# Sheet1.net
KiCad netlist of a schematic drawn in Altium Designer
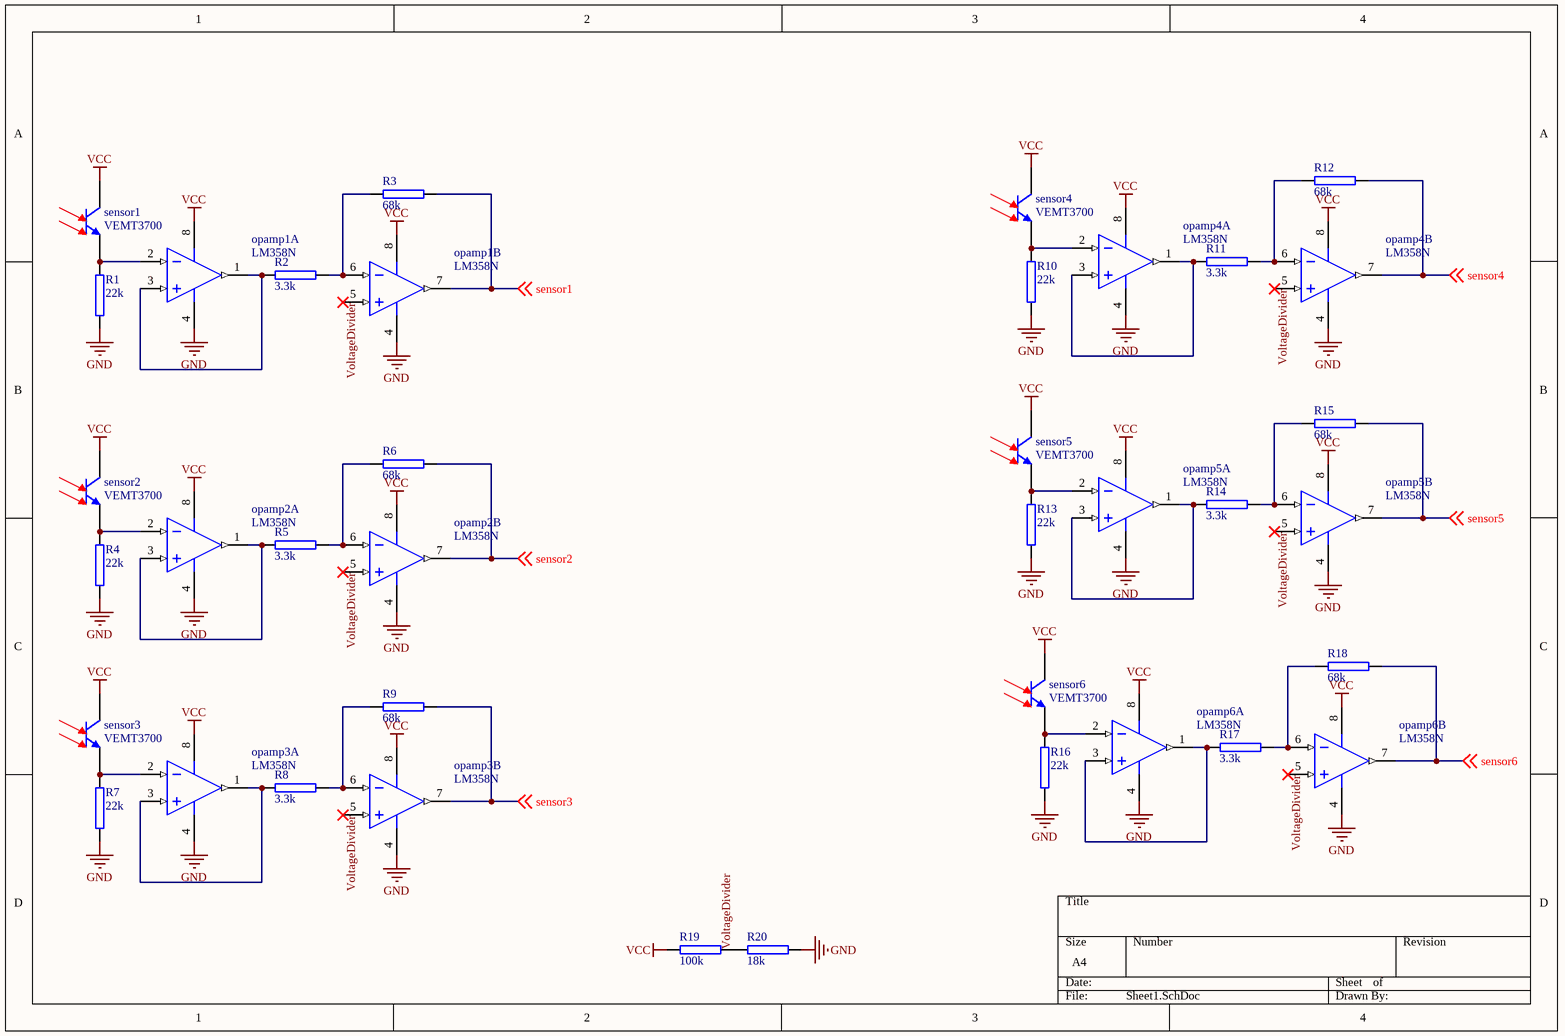
[diagram p0: Sheet1.SchDoc]

(export (version "E")
  (design (tool "Eeschema 10.0.6"))
  (components
    (comp (ref "opamp1")
      (value "LM358N")
      (footprint "N08E")
      (description "Low Power Dual Operational Amplifier, 8-pin MDIP")
      (fields
        (field (name "MANUFACTURER") "National Semiconductor")
        (field (name "PUBLISHER") "Altium Limited")
      )
      (libsource (lib "NSC Amplifier") (part "LM358N"))
    )
    (comp (ref "opamp2")
      (value "LM358N")
      (footprint "N08E")
      (description "Low Power Dual Operational Amplifier, 8-pin MDIP")
      (fields
        (field (name "MANUFACTURER") "National Semiconductor")
        (field (name "PUBLISHER") "Altium Limited")
      )
      (libsource (lib "NSC Amplifier") (part "LM358N"))
    )
    (comp (ref "opamp3")
      (value "LM358N")
      (footprint "N08E")
      (description "Low Power Dual Operational Amplifier, 8-pin MDIP")
      (fields
        (field (name "MANUFACTURER") "National Semiconductor")
        (field (name "PUBLISHER") "Altium Limited")
      )
      (libsource (lib "NSC Amplifier") (part "LM358N"))
    )
    (comp (ref "opamp4")
      (value "LM358N")
      (footprint "N08E")
      (description "Low Power Dual Operational Amplifier, 8-pin MDIP")
      (fields
        (field (name "MANUFACTURER") "National Semiconductor")
        (field (name "PUBLISHER") "Altium Limited")
      )
      (libsource (lib "NSC Amplifier") (part "LM358N"))
    )
    (comp (ref "opamp5")
      (value "LM358N")
      (footprint "N08E")
      (description "Low Power Dual Operational Amplifier, 8-pin MDIP")
      (fields
        (field (name "MANUFACTURER") "National Semiconductor")
        (field (name "PUBLISHER") "Altium Limited")
      )
      (libsource (lib "NSC Amplifier") (part "LM358N"))
    )
    (comp (ref "opamp6")
      (value "LM358N")
      (footprint "N08E")
      (description "Low Power Dual Operational Amplifier, 8-pin MDIP")
      (fields
        (field (name "MANUFACTURER") "National Semiconductor")
        (field (name "PUBLISHER") "Altium Limited")
      )
      (libsource (lib "NSC Amplifier") (part "LM358N"))
    )
    (comp (ref "R1") (value "22k") (footprint "AXIAL0.4") (libsource (lib "COMSYS301_2013") (part "RES2")))
    (comp (ref "R2") (value "3.3k") (footprint "AXIAL0.4") (libsource (lib "COMSYS301_2013") (part "RES2")))
    (comp (ref "R3") (value "68k") (footprint "AXIAL0.4") (libsource (lib "COMSYS301_2013") (part "RES2")))
    (comp (ref "R4") (value "22k") (footprint "AXIAL0.4") (libsource (lib "COMSYS301_2013") (part "RES2")))
    (comp (ref "R5") (value "3.3k") (footprint "AXIAL0.4") (libsource (lib "COMSYS301_2013") (part "RES2")))
    (comp (ref "R6") (value "68k") (footprint "AXIAL0.4") (libsource (lib "COMSYS301_2013") (part "RES2")))
    (comp (ref "R7") (value "22k") (footprint "AXIAL0.4") (libsource (lib "COMSYS301_2013") (part "RES2")))
    (comp (ref "R8") (value "3.3k") (footprint "AXIAL0.4") (libsource (lib "COMSYS301_2013") (part "RES2")))
    (comp (ref "R9") (value "68k") (footprint "AXIAL0.4") (libsource (lib "COMSYS301_2013") (part "RES2")))
    (comp (ref "R10") (value "22k") (footprint "AXIAL0.4") (libsource (lib "COMSYS301_2013") (part "RES2")))
    (comp (ref "R11") (value "3.3k") (footprint "AXIAL0.4") (libsource (lib "COMSYS301_2013") (part "RES2")))
    (comp (ref "R12") (value "68k") (footprint "AXIAL0.4") (libsource (lib "COMSYS301_2013") (part "RES2")))
    (comp (ref "R13") (value "22k") (footprint "AXIAL0.4") (libsource (lib "COMSYS301_2013") (part "RES2")))
    (comp (ref "R14") (value "3.3k") (footprint "AXIAL0.4") (libsource (lib "COMSYS301_2013") (part "RES2")))
    (comp (ref "R15") (value "68k") (footprint "AXIAL0.4") (libsource (lib "COMSYS301_2013") (part "RES2")))
    (comp (ref "R16") (value "22k") (footprint "AXIAL0.4") (libsource (lib "COMSYS301_2013") (part "RES2")))
    (comp (ref "R17") (value "3.3k") (footprint "AXIAL0.4") (libsource (lib "COMSYS301_2013") (part "RES2")))
    (comp (ref "R18") (value "68k") (footprint "AXIAL0.4") (libsource (lib "COMSYS301_2013") (part "RES2")))
    (comp (ref "R19") (value "100k") (footprint "AXIAL0.4") (libsource (lib "COMSYS301_2013") (part "RES2")))
    (comp (ref "R20") (value "18k") (footprint "AXIAL0.4") (libsource (lib "COMSYS301_2013") (part "RES2")))
    (comp (ref "sensor1")
      (value "VEMT3700")
      (footprint "VEMT3700")
      (description "Silicon NPN Phototransistor")
      (libsource (lib "COMSYS301_2013") (part "VEMT3700"))
    )
    (comp (ref "sensor2")
      (value "VEMT3700")
      (footprint "VEMT3700")
      (description "Silicon NPN Phototransistor")
      (libsource (lib "COMSYS301_2013") (part "VEMT3700"))
    )
    (comp (ref "sensor3")
      (value "VEMT3700")
      (footprint "VEMT3700")
      (description "Silicon NPN Phototransistor")
      (libsource (lib "COMSYS301_2013") (part "VEMT3700"))
    )
    (comp (ref "sensor4")
      (value "VEMT3700")
      (footprint "VEMT3700")
      (description "Silicon NPN Phototransistor")
      (libsource (lib "COMSYS301_2013") (part "VEMT3700"))
    )
    (comp (ref "sensor5")
      (value "VEMT3700")
      (footprint "VEMT3700")
      (description "Silicon NPN Phototransistor")
      (libsource (lib "COMSYS301_2013") (part "VEMT3700"))
    )
    (comp (ref "sensor6")
      (value "VEMT3700")
      (footprint "VEMT3700")
      (description "Silicon NPN Phototransistor")
      (libsource (lib "COMSYS301_2013") (part "VEMT3700"))
    )
  )
  (nets
    (net (code "1") (name "/VoltageDivider") (class "Default")
      (node (ref "R19") (pin "1") (pinfunction "1_1") (pintype "passive"))
      (node (ref "R20") (pin "1") (pinfunction "1_1") (pintype "passive"))
      (node (ref "opamp1") (pin "5") (pinfunction "INB+_5") (pintype "input"))
      (node (ref "opamp2") (pin "5") (pinfunction "INB+_5") (pintype "input"))
      (node (ref "opamp3") (pin "5") (pinfunction "INB+_5") (pintype "input"))
      (node (ref "opamp4") (pin "5") (pinfunction "INB+_5") (pintype "input"))
      (node (ref "opamp5") (pin "5") (pinfunction "INB+_5") (pintype "input"))
      (node (ref "opamp6") (pin "5") (pinfunction "INB+_5") (pintype "input"))
    )
    (net (code "2") (name "GND") (class "Default")
      (node (ref "R1") (pin "2") (pinfunction "2_2") (pintype "passive"))
      (node (ref "R10") (pin "2") (pinfunction "2_2") (pintype "passive"))
      (node (ref "R13") (pin "2") (pinfunction "2_2") (pintype "passive"))
      (node (ref "R16") (pin "2") (pinfunction "2_2") (pintype "passive"))
      (node (ref "R20") (pin "2") (pinfunction "2_2") (pintype "passive"))
      (node (ref "R4") (pin "2") (pinfunction "2_2") (pintype "passive"))
      (node (ref "R7") (pin "2") (pinfunction "2_2") (pintype "passive"))
      (node (ref "opamp1") (pin "4") (pinfunction "GND_4") (pintype "power_in"))
      (node (ref "opamp2") (pin "4") (pinfunction "GND_4") (pintype "power_in"))
      (node (ref "opamp3") (pin "4") (pinfunction "GND_4") (pintype "power_in"))
      (node (ref "opamp4") (pin "4") (pinfunction "GND_4") (pintype "power_in"))
      (node (ref "opamp5") (pin "4") (pinfunction "GND_4") (pintype "power_in"))
      (node (ref "opamp6") (pin "4") (pinfunction "GND_4") (pintype "power_in"))
    )
    (net (code "3") (name "Net-(opamp1A-INA+)") (class "Default")
      (node (ref "R2") (pin "1") (pinfunction "1_1") (pintype "passive"))
      (node (ref "opamp1") (pin "1") (pinfunction "OUTA_1") (pintype "output"))
      (node (ref "opamp1") (pin "3") (pinfunction "INA+_3") (pintype "input"))
    )
    (net (code "4") (name "Net-(opamp1A-INA-)") (class "Default")
      (node (ref "R1") (pin "1") (pinfunction "1_1") (pintype "passive"))
      (node (ref "opamp1") (pin "2") (pinfunction "INA-_2") (pintype "input"))
      (node (ref "sensor1") (pin "2") (pinfunction "E_2") (pintype "passive"))
    )
    (net (code "5") (name "Net-(opamp1B-INB-)") (class "Default")
      (node (ref "R2") (pin "2") (pinfunction "2_2") (pintype "passive"))
      (node (ref "R3") (pin "1") (pinfunction "1_1") (pintype "passive"))
      (node (ref "opamp1") (pin "6") (pinfunction "INB-_6") (pintype "input"))
    )
    (net (code "6") (name "Net-(opamp2A-INA+)") (class "Default")
      (node (ref "R5") (pin "1") (pinfunction "1_1") (pintype "passive"))
      (node (ref "opamp2") (pin "1") (pinfunction "OUTA_1") (pintype "output"))
      (node (ref "opamp2") (pin "3") (pinfunction "INA+_3") (pintype "input"))
    )
    (net (code "7") (name "Net-(opamp2A-INA-)") (class "Default")
      (node (ref "R4") (pin "1") (pinfunction "1_1") (pintype "passive"))
      (node (ref "opamp2") (pin "2") (pinfunction "INA-_2") (pintype "input"))
      (node (ref "sensor2") (pin "2") (pinfunction "E_2") (pintype "passive"))
    )
    (net (code "8") (name "Net-(opamp2B-INB-)") (class "Default")
      (node (ref "R5") (pin "2") (pinfunction "2_2") (pintype "passive"))
      (node (ref "R6") (pin "1") (pinfunction "1_1") (pintype "passive"))
      (node (ref "opamp2") (pin "6") (pinfunction "INB-_6") (pintype "input"))
    )
    (net (code "9") (name "Net-(opamp3A-INA+)") (class "Default")
      (node (ref "R8") (pin "1") (pinfunction "1_1") (pintype "passive"))
      (node (ref "opamp3") (pin "1") (pinfunction "OUTA_1") (pintype "output"))
      (node (ref "opamp3") (pin "3") (pinfunction "INA+_3") (pintype "input"))
    )
    (net (code "10") (name "Net-(opamp3A-INA-)") (class "Default")
      (node (ref "R7") (pin "1") (pinfunction "1_1") (pintype "passive"))
      (node (ref "opamp3") (pin "2") (pinfunction "INA-_2") (pintype "input"))
      (node (ref "sensor3") (pin "2") (pinfunction "E_2") (pintype "passive"))
    )
    (net (code "11") (name "Net-(opamp3B-INB-)") (class "Default")
      (node (ref "R8") (pin "2") (pinfunction "2_2") (pintype "passive"))
      (node (ref "R9") (pin "1") (pinfunction "1_1") (pintype "passive"))
      (node (ref "opamp3") (pin "6") (pinfunction "INB-_6") (pintype "input"))
    )
    (net (code "12") (name "Net-(opamp4A-INA+)") (class "Default")
      (node (ref "R11") (pin "1") (pinfunction "1_1") (pintype "passive"))
      (node (ref "opamp4") (pin "1") (pinfunction "OUTA_1") (pintype "output"))
      (node (ref "opamp4") (pin "3") (pinfunction "INA+_3") (pintype "input"))
    )
    (net (code "13") (name "Net-(opamp4A-INA-)") (class "Default")
      (node (ref "R10") (pin "1") (pinfunction "1_1") (pintype "passive"))
      (node (ref "opamp4") (pin "2") (pinfunction "INA-_2") (pintype "input"))
      (node (ref "sensor4") (pin "2") (pinfunction "E_2") (pintype "passive"))
    )
    (net (code "14") (name "Net-(opamp4B-INB-)") (class "Default")
      (node (ref "R11") (pin "2") (pinfunction "2_2") (pintype "passive"))
      (node (ref "R12") (pin "1") (pinfunction "1_1") (pintype "passive"))
      (node (ref "opamp4") (pin "6") (pinfunction "INB-_6") (pintype "input"))
    )
    (net (code "15") (name "Net-(opamp5A-INA+)") (class "Default")
      (node (ref "R14") (pin "1") (pinfunction "1_1") (pintype "passive"))
      (node (ref "opamp5") (pin "1") (pinfunction "OUTA_1") (pintype "output"))
      (node (ref "opamp5") (pin "3") (pinfunction "INA+_3") (pintype "input"))
    )
    (net (code "16") (name "Net-(opamp5A-INA-)") (class "Default")
      (node (ref "R13") (pin "1") (pinfunction "1_1") (pintype "passive"))
      (node (ref "opamp5") (pin "2") (pinfunction "INA-_2") (pintype "input"))
      (node (ref "sensor5") (pin "2") (pinfunction "E_2") (pintype "passive"))
    )
    (net (code "17") (name "Net-(opamp5B-INB-)") (class "Default")
      (node (ref "R14") (pin "2") (pinfunction "2_2") (pintype "passive"))
      (node (ref "R15") (pin "1") (pinfunction "1_1") (pintype "passive"))
      (node (ref "opamp5") (pin "6") (pinfunction "INB-_6") (pintype "input"))
    )
    (net (code "18") (name "Net-(opamp6A-INA+)") (class "Default")
      (node (ref "R17") (pin "1") (pinfunction "1_1") (pintype "passive"))
      (node (ref "opamp6") (pin "1") (pinfunction "OUTA_1") (pintype "output"))
      (node (ref "opamp6") (pin "3") (pinfunction "INA+_3") (pintype "input"))
    )
    (net (code "19") (name "Net-(opamp6A-INA-)") (class "Default")
      (node (ref "R16") (pin "1") (pinfunction "1_1") (pintype "passive"))
      (node (ref "opamp6") (pin "2") (pinfunction "INA-_2") (pintype "input"))
      (node (ref "sensor6") (pin "2") (pinfunction "E_2") (pintype "passive"))
    )
    (net (code "20") (name "Net-(opamp6B-INB-)") (class "Default")
      (node (ref "R17") (pin "2") (pinfunction "2_2") (pintype "passive"))
      (node (ref "R18") (pin "1") (pinfunction "1_1") (pintype "passive"))
      (node (ref "opamp6") (pin "6") (pinfunction "INB-_6") (pintype "input"))
    )
    (net (code "21") (name "VCC") (class "Default")
      (node (ref "R19") (pin "2") (pinfunction "2_2") (pintype "passive"))
      (node (ref "opamp1") (pin "8") (pinfunction "V+_8") (pintype "power_in"))
      (node (ref "opamp2") (pin "8") (pinfunction "V+_8") (pintype "power_in"))
      (node (ref "opamp3") (pin "8") (pinfunction "V+_8") (pintype "power_in"))
      (node (ref "opamp4") (pin "8") (pinfunction "V+_8") (pintype "power_in"))
      (node (ref "opamp5") (pin "8") (pinfunction "V+_8") (pintype "power_in"))
      (node (ref "opamp6") (pin "8") (pinfunction "V+_8") (pintype "power_in"))
      (node (ref "sensor1") (pin "1") (pinfunction "C_1") (pintype "passive"))
      (node (ref "sensor2") (pin "1") (pinfunction "C_1") (pintype "passive"))
      (node (ref "sensor3") (pin "1") (pinfunction "C_1") (pintype "passive"))
      (node (ref "sensor4") (pin "1") (pinfunction "C_1") (pintype "passive"))
      (node (ref "sensor5") (pin "1") (pinfunction "C_1") (pintype "passive"))
      (node (ref "sensor6") (pin "1") (pinfunction "C_1") (pintype "passive"))
    )
    (net (code "22") (name "sensor1") (class "Default")
      (node (ref "R3") (pin "2") (pinfunction "2_2") (pintype "passive"))
      (node (ref "opamp1") (pin "7") (pinfunction "OUTB_7") (pintype "output"))
    )
    (net (code "23") (name "sensor2") (class "Default")
      (node (ref "R6") (pin "2") (pinfunction "2_2") (pintype "passive"))
      (node (ref "opamp2") (pin "7") (pinfunction "OUTB_7") (pintype "output"))
    )
    (net (code "24") (name "sensor3") (class "Default")
      (node (ref "R9") (pin "2") (pinfunction "2_2") (pintype "passive"))
      (node (ref "opamp3") (pin "7") (pinfunction "OUTB_7") (pintype "output"))
    )
    (net (code "25") (name "sensor4") (class "Default")
      (node (ref "R12") (pin "2") (pinfunction "2_2") (pintype "passive"))
      (node (ref "opamp4") (pin "7") (pinfunction "OUTB_7") (pintype "output"))
    )
    (net (code "26") (name "sensor5") (class "Default")
      (node (ref "R15") (pin "2") (pinfunction "2_2") (pintype "passive"))
      (node (ref "opamp5") (pin "7") (pinfunction "OUTB_7") (pintype "output"))
    )
    (net (code "27") (name "sensor6") (class "Default")
      (node (ref "R18") (pin "2") (pinfunction "2_2") (pintype "passive"))
      (node (ref "opamp6") (pin "7") (pinfunction "OUTB_7") (pintype "output"))
    )
  )
)
